# AVS.net
KiCad netlist of a schematic drawn in EasyEDA
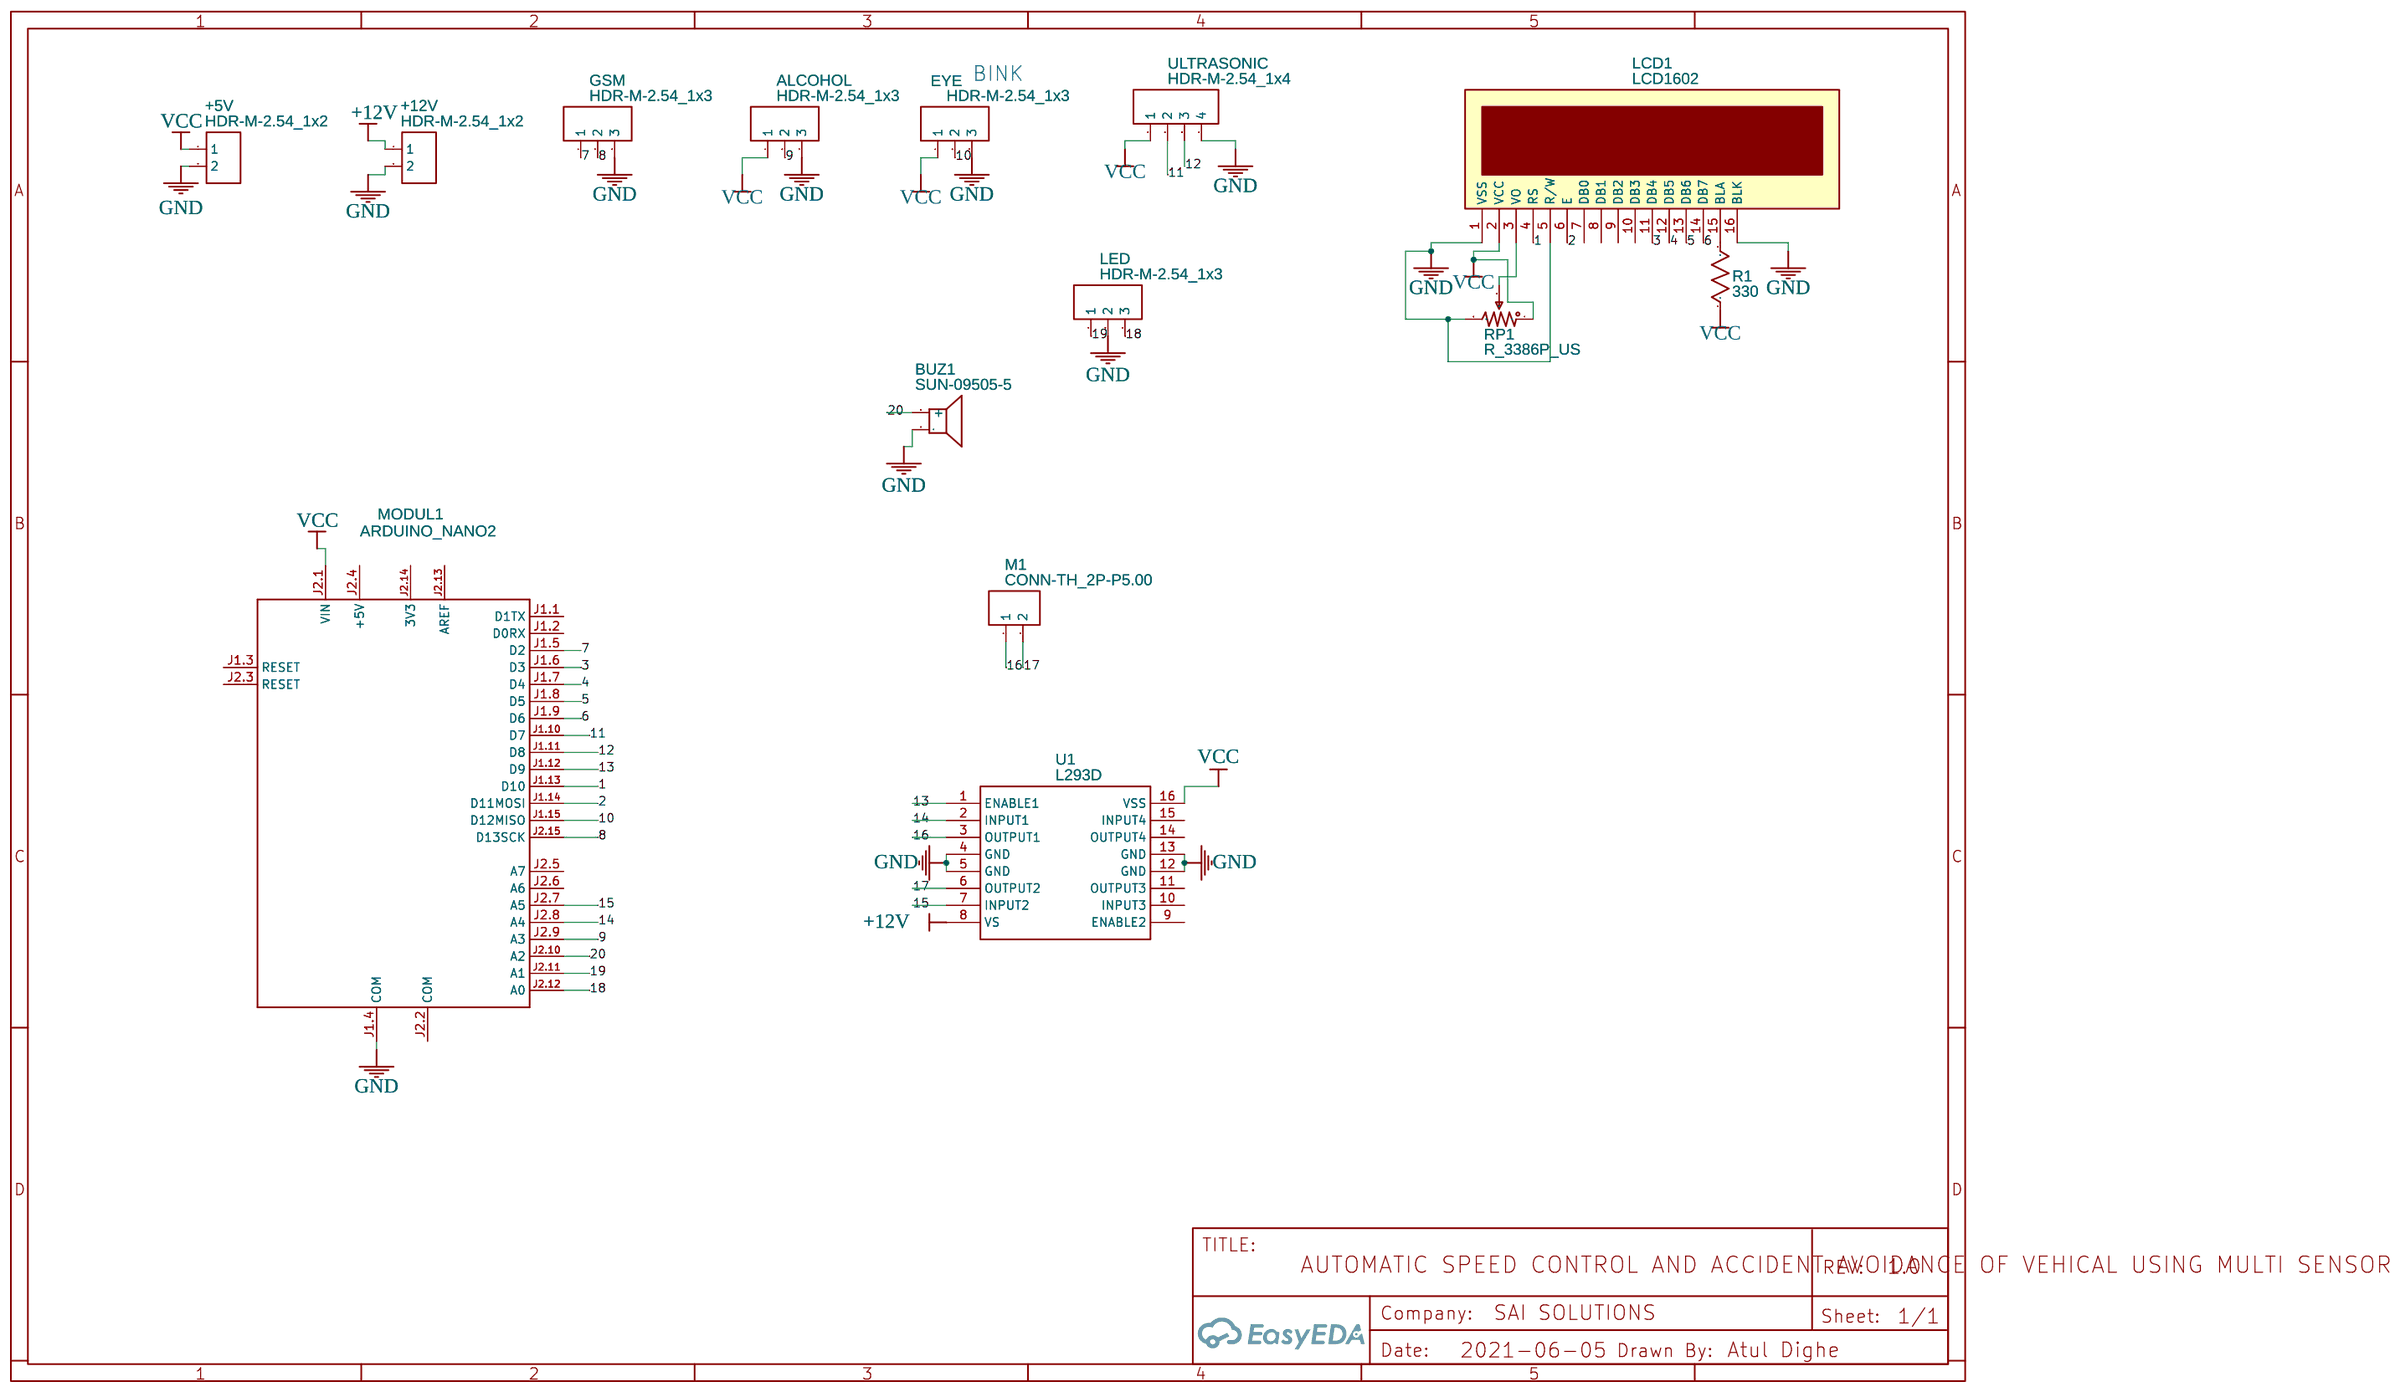
[diagram p0: CONTROLLER BOARD]
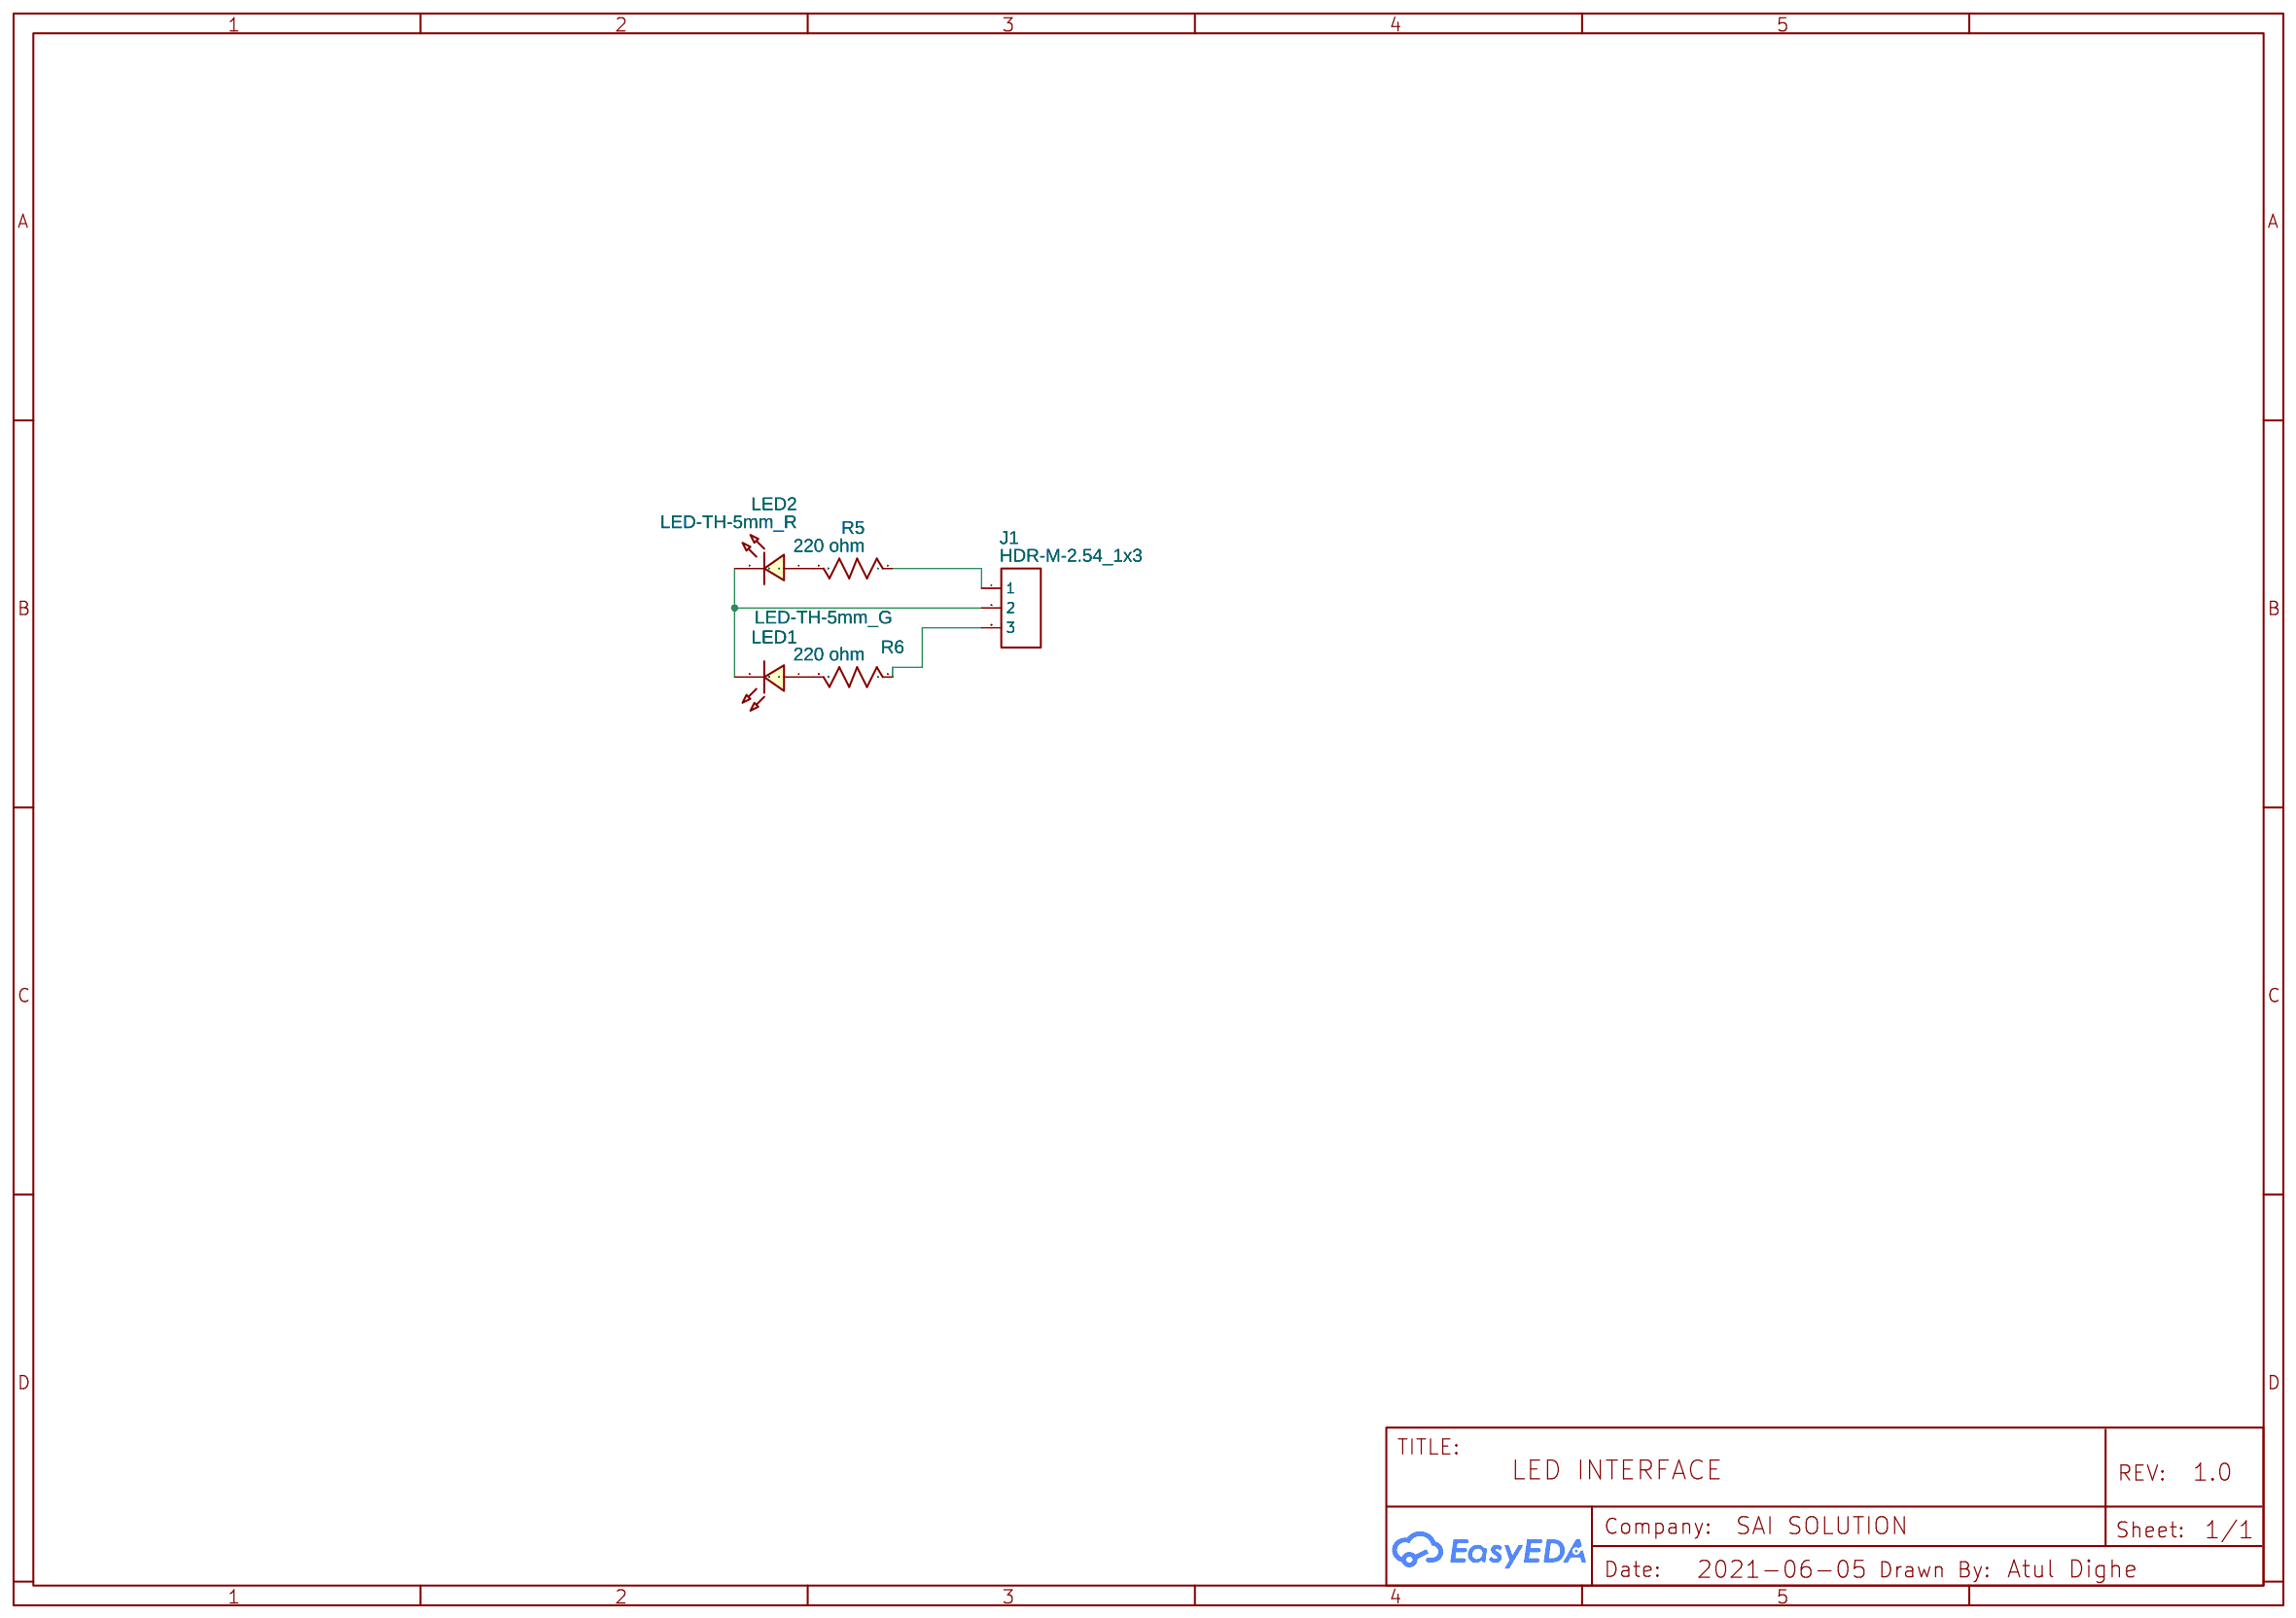
[diagram p1: LED INTERFACE]

(export (version "E")
  (design (tool "Eeschema 10.0.6"))
  (components
    (comp (ref "+5V")
      (value "HDR-M-2.54_1x2")
      (fields (field (name "BOM_Supplier Part") "C124375"))
      (libsource (lib "") (part "HDR-M-2.54_1x2"))
    )
    (comp (ref "+12V")
      (value "HDR-M-2.54_1x2")
      (fields (field (name "BOM_Supplier Part") "C124375"))
      (libsource (lib "") (part "HDR-M-2.54_1x2_1"))
    )
    (comp (ref "ALCOHOL")
      (value "HDR-M-2.54_1x3")
      (fields (field (name "BOM_Supplier Part") "C180248"))
      (libsource (lib "") (part "HDR-M-2.54_1x3_2"))
    )
    (comp (ref "BUZ1")
      (value "SUN-09505-5")
      (fields (field (name "BOM_Supplier Part") "C2862"))
      (libsource (lib "") (part "SUN-09505-5"))
    )
    (comp (ref "EYE")
      (value "HDR-M-2.54_1x3")
      (fields (field (name "BOM_Supplier Part") "C180248"))
      (libsource (lib "") (part "HDR-M-2.54_1x3_3"))
    )
    (comp (ref "GSM")
      (value "HDR-M-2.54_1x3")
      (fields (field (name "BOM_Supplier Part") "C180248"))
      (libsource (lib "") (part "HDR-M-2.54_1x3"))
    )
    (comp (ref "LCD1")
      (value "LCD1602")
      (fields
        (field (name "BOM_Manufacturer Part") "LCM1602K-NSW-BBW")
        (field (name "BOM_Supplier Part") "C83275")
      )
      (libsource (lib "") (part "LCD1602"))
    )
    (comp (ref "LED")
      (value "HDR-M-2.54_1x3")
      (fields (field (name "BOM_Supplier Part") "C180248"))
      (libsource (lib "") (part "HDR-M-2.54_1x3_1"))
    )
    (comp (ref "M1") (value "CONN-TH_2P-P5.00") (libsource (lib "") (part "CONN-TH_2P-P5.00")))
    (comp (ref "MODUL1") (value "ARDUINO_NANO2") (libsource (lib "") (part "ARDUINO_NANO2")))
    (comp (ref "R1") (value "330") (libsource (lib "") (part "R_AXIAL-0.4_US")))
    (comp (ref "RP1") (value "R_3386P_US") (libsource (lib "") (part "R_3386P_US")))
    (comp (ref "U1")
      (value "L293D")
      (fields (field (name "BOM_Supplier Part") "C12340"))
      (libsource (lib "") (part "L293D"))
    )
    (comp (ref "ULTRASONIC")
      (value "HDR-M-2.54_1x4")
      (fields (field (name "BOM_Supplier Part") "C124378"))
      (libsource (lib "") (part "HDR-M-2.54_1x4"))
    )
    (comp (ref "J1")
      (value "HDR-M-2.54_1x3")
      (fields (field (name "BOM_Supplier Part") "C180248"))
      (libsource (lib "") (part "HDR-M-2.54_1x3"))
    )
    (comp (ref "LED1")
      (value "LED-TH-5mm_G")
      (fields
        (field (name "BOM_Manufacturer Part") "333-2SYGD/S530-E2")
        (field (name "BOM_Supplier Part") "C88163")
      )
      (libsource (lib "") (part "LED-TH-5mm_G"))
    )
    (comp (ref "LED2")
      (value "LED-TH-5mm_R")
      (fields
        (field (name "BOM_Manufacturer Part") "333-2SURD/S530-A3")
        (field (name "BOM_Supplier Part") "C87271")
      )
      (libsource (lib "") (part "LED-TH-5mm_R"))
    )
    (comp (ref "R5") (value "220 ohm") (libsource (lib "") (part "R_AXIAL-0.4_US")))
    (comp (ref "R6") (value "220 ohm") (libsource (lib "") (part "R_AXIAL-0.4_US")))
  )
  (nets
    (net (code "1") (name "+12V") (class "Default")
      (node (ref "+12V") (pin "1") (pinfunction "1_1") (pintype "unspecified"))
      (node (ref "U1") (pin "8") (pinfunction "VS_8") (pintype "unspecified"))
    )
    (net (code "2") (name "1") (class "Default")
      (node (ref "LCD1") (pin "4") (pinfunction "RS_4") (pintype "unspecified"))
      (node (ref "MODUL1") (pin "J1.13") (pinfunction "D10_J1.13") (pintype "unspecified"))
    )
    (net (code "3") (name "2") (class "Default")
      (node (ref "LCD1") (pin "6") (pinfunction "E_6") (pintype "unspecified"))
      (node (ref "MODUL1") (pin "J1.14") (pinfunction "D11MOSI_J1.14") (pintype "unspecified"))
    )
    (net (code "4") (name "3") (class "Default")
      (node (ref "LCD1") (pin "11") (pinfunction "DB4_11") (pintype "unspecified"))
      (node (ref "MODUL1") (pin "J1.6") (pinfunction "D3_J1.6") (pintype "unspecified"))
    )
    (net (code "5") (name "4") (class "Default")
      (node (ref "LCD1") (pin "12") (pinfunction "DB5_12") (pintype "unspecified"))
      (node (ref "MODUL1") (pin "J1.7") (pinfunction "D4_J1.7") (pintype "unspecified"))
    )
    (net (code "6") (name "5") (class "Default")
      (node (ref "LCD1") (pin "13") (pinfunction "DB6_13") (pintype "unspecified"))
      (node (ref "MODUL1") (pin "J1.8") (pinfunction "D5_J1.8") (pintype "unspecified"))
    )
    (net (code "7") (name "6") (class "Default")
      (node (ref "LCD1") (pin "14") (pinfunction "DB7_14") (pintype "unspecified"))
      (node (ref "MODUL1") (pin "J1.9") (pinfunction "D6_J1.9") (pintype "unspecified"))
    )
    (net (code "8") (name "7") (class "Default")
      (node (ref "GSM") (pin "1") (pinfunction "1_1") (pintype "input"))
      (node (ref "MODUL1") (pin "J1.5") (pinfunction "D2_J1.5") (pintype "unspecified"))
    )
    (net (code "9") (name "8") (class "Default")
      (node (ref "GSM") (pin "2") (pinfunction "2_2") (pintype "input"))
      (node (ref "MODUL1") (pin "J2.15") (pinfunction "D13SCK_J2.15") (pintype "unspecified"))
    )
    (net (code "10") (name "9") (class "Default")
      (node (ref "ALCOHOL") (pin "2") (pinfunction "2_2") (pintype "input"))
      (node (ref "MODUL1") (pin "J2.9") (pinfunction "A3_J2.9") (pintype "unspecified"))
    )
    (net (code "11") (name "10") (class "Default")
      (node (ref "EYE") (pin "2") (pinfunction "2_2") (pintype "input"))
      (node (ref "MODUL1") (pin "J1.15") (pinfunction "D12MISO_J1.15") (pintype "unspecified"))
    )
    (net (code "12") (name "11") (class "Default")
      (node (ref "MODUL1") (pin "J1.10") (pinfunction "D7_J1.10") (pintype "unspecified"))
      (node (ref "ULTRASONIC") (pin "2") (pinfunction "2_2") (pintype "unspecified"))
    )
    (net (code "13") (name "12") (class "Default")
      (node (ref "MODUL1") (pin "J1.11") (pinfunction "D8_J1.11") (pintype "unspecified"))
      (node (ref "ULTRASONIC") (pin "3") (pinfunction "3_3") (pintype "unspecified"))
    )
    (net (code "14") (name "13") (class "Default")
      (node (ref "MODUL1") (pin "J1.12") (pinfunction "D9_J1.12") (pintype "unspecified"))
      (node (ref "U1") (pin "1") (pinfunction "ENABLE1_1") (pintype "unspecified"))
    )
    (net (code "15") (name "14") (class "Default")
      (node (ref "MODUL1") (pin "J2.8") (pinfunction "A4_J2.8") (pintype "unspecified"))
      (node (ref "U1") (pin "2") (pinfunction "INPUT1_2") (pintype "unspecified"))
    )
    (net (code "16") (name "15") (class "Default")
      (node (ref "MODUL1") (pin "J2.7") (pinfunction "A5_J2.7") (pintype "unspecified"))
      (node (ref "U1") (pin "7") (pinfunction "INPUT2_7") (pintype "unspecified"))
    )
    (net (code "17") (name "16") (class "Default")
      (node (ref "M1") (pin "1") (pinfunction "1_1") (pintype "unspecified"))
      (node (ref "U1") (pin "3") (pinfunction "OUTPUT1_3") (pintype "unspecified"))
    )
    (net (code "18") (name "17") (class "Default")
      (node (ref "M1") (pin "2") (pinfunction "2_2") (pintype "unspecified"))
      (node (ref "U1") (pin "6") (pinfunction "OUTPUT2_6") (pintype "unspecified"))
    )
    (net (code "19") (name "18") (class "Default")
      (node (ref "LED") (pin "3") (pinfunction "3_3") (pintype "input"))
      (node (ref "MODUL1") (pin "J2.12") (pinfunction "A0_J2.12") (pintype "unspecified"))
    )
    (net (code "20") (name "19") (class "Default")
      (node (ref "LED") (pin "1") (pinfunction "1_1") (pintype "input"))
      (node (ref "MODUL1") (pin "J2.11") (pinfunction "A1_J2.11") (pintype "unspecified"))
    )
    (net (code "21") (name "20") (class "Default")
      (node (ref "BUZ1") (pin "1") (pinfunction "+_1") (pintype "unspecified"))
      (node (ref "MODUL1") (pin "J2.10") (pinfunction "A2_J2.10") (pintype "unspecified"))
    )
    (net (code "22") (name "GND") (class "Default")
      (node (ref "+12V") (pin "2") (pinfunction "2_2") (pintype "unspecified"))
      (node (ref "+5V") (pin "2") (pinfunction "2_2") (pintype "unspecified"))
      (node (ref "ALCOHOL") (pin "3") (pinfunction "3_3") (pintype "input"))
      (node (ref "BUZ1") (pin "2") (pinfunction "2_2") (pintype "unspecified"))
      (node (ref "EYE") (pin "3") (pinfunction "3_3") (pintype "input"))
      (node (ref "GSM") (pin "3") (pinfunction "3_3") (pintype "input"))
      (node (ref "LCD1") (pin "1") (pinfunction "VSS_1") (pintype "unspecified"))
      (node (ref "LCD1") (pin "16") (pinfunction "BLK_16") (pintype "unspecified"))
      (node (ref "LCD1") (pin "5") (pinfunction "R/W_5") (pintype "unspecified"))
      (node (ref "LED") (pin "2") (pinfunction "2_2") (pintype "input"))
      (node (ref "MODUL1") (pin "J1.4") (pinfunction "COM_J1.4") (pintype "passive"))
      (node (ref "RP1") (pin "3") (pinfunction "3_3") (pintype "unspecified"))
      (node (ref "U1") (pin "12") (pinfunction "GND_12") (pintype "unspecified"))
      (node (ref "U1") (pin "13") (pinfunction "GND_13") (pintype "unspecified"))
      (node (ref "U1") (pin "4") (pinfunction "GND_4") (pintype "unspecified"))
      (node (ref "U1") (pin "5") (pinfunction "GND_5") (pintype "unspecified"))
      (node (ref "ULTRASONIC") (pin "4") (pinfunction "4_4") (pintype "unspecified"))
    )
    (net (code "23") (name "Net-(J1-Pad1)") (class "Default")
      (node (ref "J1") (pin "1") (pinfunction "1_1") (pintype "input"))
      (node (ref "R5") (pin "1") (pinfunction "1_1") (pintype "unspecified"))
    )
    (net (code "24") (name "Net-(J1-Pad2)") (class "Default")
      (node (ref "J1") (pin "2") (pinfunction "2_2") (pintype "input"))
      (node (ref "LED1") (pin "2") (pinfunction "2_2") (pintype "unspecified"))
      (node (ref "LED2") (pin "2") (pinfunction "2_2") (pintype "unspecified"))
    )
    (net (code "25") (name "Net-(J1-Pad3)") (class "Default")
      (node (ref "J1") (pin "3") (pinfunction "3_3") (pintype "input"))
      (node (ref "R6") (pin "1") (pinfunction "1_1") (pintype "unspecified"))
    )
    (net (code "26") (name "Net-(LCD1-BLA)") (class "Default")
      (node (ref "LCD1") (pin "15") (pinfunction "BLA_15") (pintype "unspecified"))
      (node (ref "R1") (pin "2") (pinfunction "2_2") (pintype "unspecified"))
    )
    (net (code "27") (name "Net-(LCD1-VO)") (class "Default")
      (node (ref "LCD1") (pin "3") (pinfunction "VO_3") (pintype "unspecified"))
      (node (ref "RP1") (pin "2") (pinfunction "2_2") (pintype "unspecified"))
    )
    (net (code "28") (name "Net-(LED1-Pad1)") (class "Default")
      (node (ref "LED1") (pin "1") (pinfunction "1_1") (pintype "unspecified"))
      (node (ref "R6") (pin "2") (pinfunction "2_2") (pintype "unspecified"))
    )
    (net (code "29") (name "Net-(LED2-Pad1)") (class "Default")
      (node (ref "LED2") (pin "1") (pinfunction "1_1") (pintype "unspecified"))
      (node (ref "R5") (pin "2") (pinfunction "2_2") (pintype "unspecified"))
    )
    (net (code "30") (name "VCC") (class "Default")
      (node (ref "+5V") (pin "1") (pinfunction "1_1") (pintype "unspecified"))
      (node (ref "ALCOHOL") (pin "1") (pinfunction "1_1") (pintype "input"))
      (node (ref "EYE") (pin "1") (pinfunction "1_1") (pintype "input"))
      (node (ref "LCD1") (pin "2") (pinfunction "VCC_2") (pintype "unspecified"))
      (node (ref "MODUL1") (pin "J2.1") (pinfunction "VIN_J2.1") (pintype "passive"))
      (node (ref "R1") (pin "1") (pinfunction "1_1") (pintype "unspecified"))
      (node (ref "RP1") (pin "1") (pinfunction "1_1") (pintype "unspecified"))
      (node (ref "U1") (pin "16") (pinfunction "VSS_16") (pintype "unspecified"))
      (node (ref "ULTRASONIC") (pin "1") (pinfunction "1_1") (pintype "unspecified"))
    )
    (net (code "31") (name "unconnected-(LCD1-DB0-Pad7)") (class "Default")
      (node (ref "LCD1") (pin "7") (pinfunction "DB0_7") (pintype "unspecified"))
    )
    (net (code "32") (name "unconnected-(LCD1-DB1-Pad8)") (class "Default")
      (node (ref "LCD1") (pin "8") (pinfunction "DB1_8") (pintype "unspecified"))
    )
    (net (code "33") (name "unconnected-(LCD1-DB2-Pad9)") (class "Default")
      (node (ref "LCD1") (pin "9") (pinfunction "DB2_9") (pintype "unspecified"))
    )
    (net (code "34") (name "unconnected-(LCD1-DB3-Pad10)") (class "Default")
      (node (ref "LCD1") (pin "10") (pinfunction "DB3_10") (pintype "unspecified"))
    )
    (net (code "35") (name "unconnected-(MODUL1-+5V-PadJ2.4)") (class "Default")
      (node (ref "MODUL1") (pin "J2.4") (pinfunction "+5V_J2.4") (pintype "passive"))
    )
    (net (code "36") (name "unconnected-(MODUL1-3V3-PadJ2.14)") (class "Default")
      (node (ref "MODUL1") (pin "J2.14") (pinfunction "3V3_J2.14") (pintype "passive"))
    )
    (net (code "37") (name "unconnected-(MODUL1-A6-PadJ2.6)") (class "Default")
      (node (ref "MODUL1") (pin "J2.6") (pinfunction "A6_J2.6") (pintype "unspecified"))
    )
    (net (code "38") (name "unconnected-(MODUL1-A7-PadJ2.5)") (class "Default")
      (node (ref "MODUL1") (pin "J2.5") (pinfunction "A7_J2.5") (pintype "unspecified"))
    )
    (net (code "39") (name "unconnected-(MODUL1-AREF-PadJ2.13)") (class "Default")
      (node (ref "MODUL1") (pin "J2.13") (pinfunction "AREF_J2.13") (pintype "passive"))
    )
    (net (code "40") (name "unconnected-(MODUL1-COM-PadJ2.2)") (class "Default")
      (node (ref "MODUL1") (pin "J2.2") (pinfunction "COM_J2.2") (pintype "passive"))
    )
    (net (code "41") (name "unconnected-(MODUL1-D0RX-PadJ1.2)") (class "Default")
      (node (ref "MODUL1") (pin "J1.2") (pinfunction "D0RX_J1.2") (pintype "unspecified"))
    )
    (net (code "42") (name "unconnected-(MODUL1-D1TX-PadJ1.1)") (class "Default")
      (node (ref "MODUL1") (pin "J1.1") (pinfunction "D1TX_J1.1") (pintype "unspecified"))
    )
    (net (code "43") (name "unconnected-(MODUL1-RESET-PadJ1.3)") (class "Default")
      (node (ref "MODUL1") (pin "J1.3") (pinfunction "RESET_J1.3") (pintype "unspecified"))
    )
    (net (code "44") (name "unconnected-(MODUL1-RESET-PadJ2.3)") (class "Default")
      (node (ref "MODUL1") (pin "J2.3") (pinfunction "RESET_J2.3") (pintype "unspecified"))
    )
    (net (code "45") (name "unconnected-(U1-ENABLE2-Pad9)") (class "Default")
      (node (ref "U1") (pin "9") (pinfunction "ENABLE2_9") (pintype "unspecified"))
    )
    (net (code "46") (name "unconnected-(U1-INPUT3-Pad10)") (class "Default")
      (node (ref "U1") (pin "10") (pinfunction "INPUT3_10") (pintype "unspecified"))
    )
    (net (code "47") (name "unconnected-(U1-INPUT4-Pad15)") (class "Default")
      (node (ref "U1") (pin "15") (pinfunction "INPUT4_15") (pintype "unspecified"))
    )
    (net (code "48") (name "unconnected-(U1-OUTPUT3-Pad11)") (class "Default")
      (node (ref "U1") (pin "11") (pinfunction "OUTPUT3_11") (pintype "unspecified"))
    )
    (net (code "49") (name "unconnected-(U1-OUTPUT4-Pad14)") (class "Default")
      (node (ref "U1") (pin "14") (pinfunction "OUTPUT4_14") (pintype "unspecified"))
    )
  )
)
